# ARMBAND.net
KiCad netlist of a schematic drawn in Altium Designer
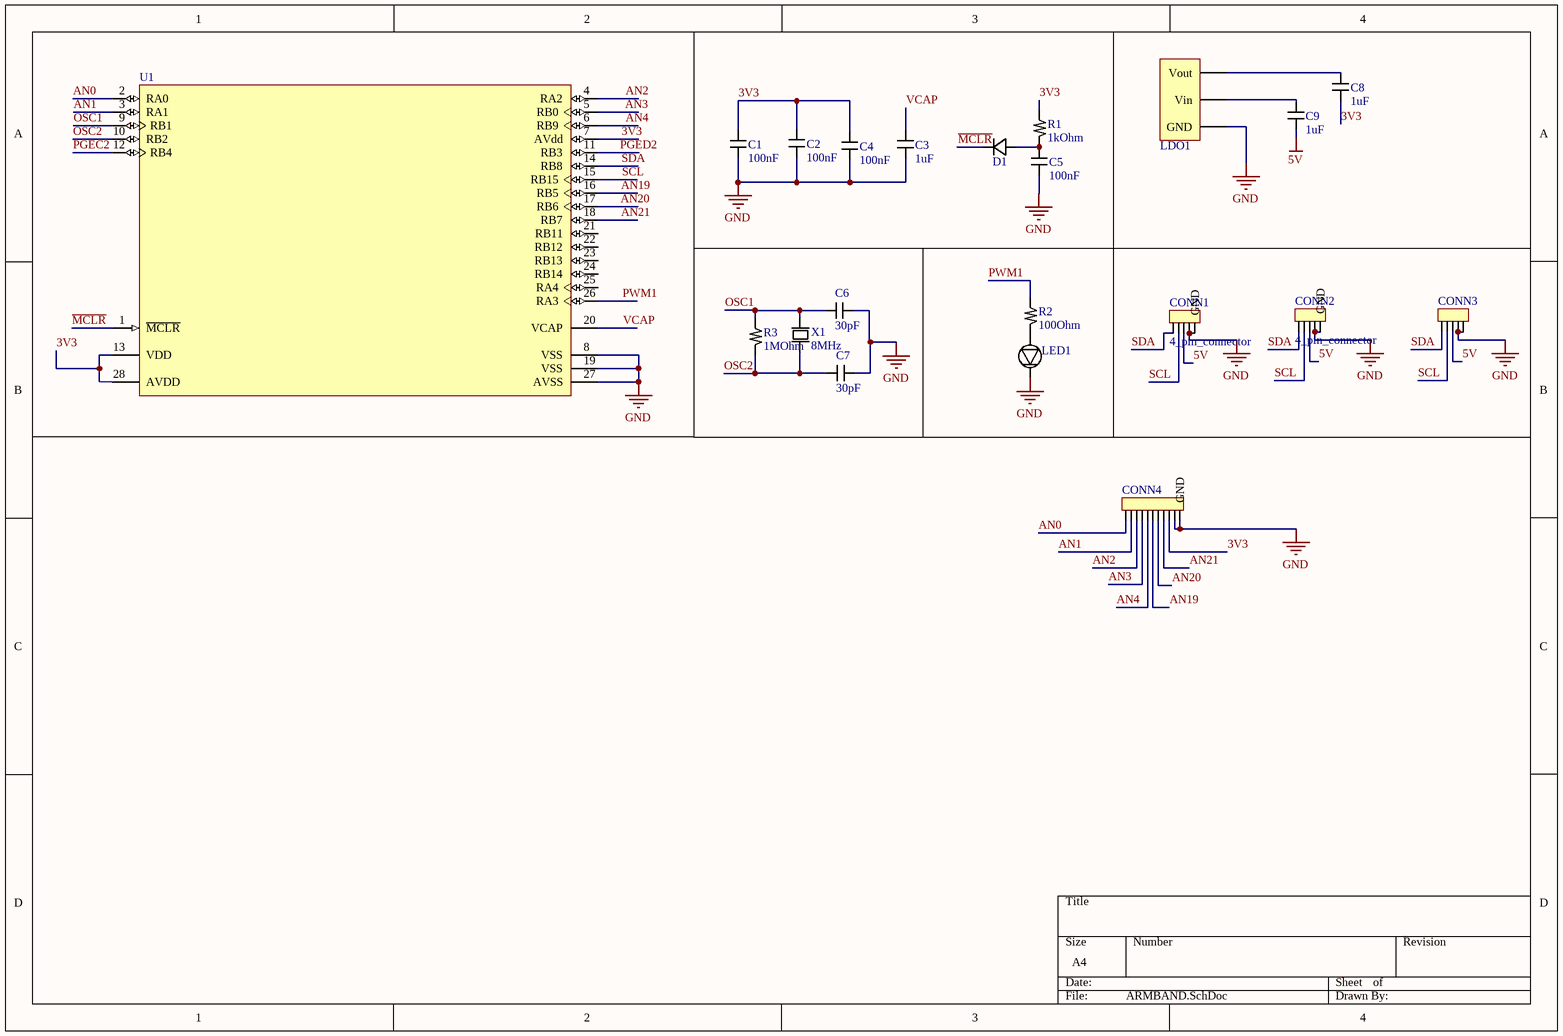
[diagram p0: ARMBAND.SchDoc]

(export (version "E")
  (design (tool "Eeschema 10.0.6"))
  (components
    (comp (ref "C1")
      (value "100nF")
      (footprint "CApacitor_1608")
      (description "SMD Capacitor")
      (libsource (lib "ARMBand_Components") (part "Capacitor_SMD"))
    )
    (comp (ref "C2")
      (value "100nF")
      (footprint "CApacitor_1608")
      (description "SMD Capacitor")
      (libsource (lib "ARMBand_Components") (part "Capacitor_SMD"))
    )
    (comp (ref "C3")
      (value "1uF")
      (footprint "Capacitor_20x12")
      (description "SMD Capacitor")
      (libsource (lib "ARMBand_Components") (part "Capacitor_SMD"))
    )
    (comp (ref "C4")
      (value "100nF")
      (footprint "CApacitor_1608")
      (description "SMD Capacitor")
      (libsource (lib "ARMBand_Components") (part "Capacitor_SMD"))
    )
    (comp (ref "C5")
      (value "100nF")
      (footprint "CApacitor_1608")
      (description "SMD Capacitor")
      (libsource (lib "ARMBand_Components") (part "Capacitor_SMD"))
    )
    (comp (ref "C6")
      (value "30pF")
      (footprint "CApacitor_1608")
      (description "SMD Capacitor")
      (libsource (lib "ARMBand_Components") (part "Capacitor_SMD"))
    )
    (comp (ref "C7")
      (value "30pF")
      (footprint "CApacitor_1608")
      (description "SMD Capacitor")
      (libsource (lib "ARMBand_Components") (part "Capacitor_SMD"))
    )
    (comp (ref "C8")
      (value "1uF")
      (footprint "Capacitor_20x12")
      (description "SMD Capacitor")
      (libsource (lib "ARMBand_Components") (part "Capacitor_SMD"))
    )
    (comp (ref "C9")
      (value "1uF")
      (footprint "Capacitor_20x12")
      (description "SMD Capacitor")
      (libsource (lib "ARMBand_Components") (part "Capacitor_SMD"))
    )
    (comp (ref "CONN1")
      (value "4_pin_connector")
      (footprint "4PIN_1MMPITCH_FFC_FCP_ZIF")
      (description "4 Pin Connector")
      (libsource (lib "") (part "4_pin_connector_1"))
    )
    (comp (ref "CONN2")
      (value "4_pin_connector")
      (footprint "4PIN_1MMPITCH_FFC_FCP_ZIF")
      (description "4 Pin Connector")
      (libsource (lib "") (part "4_pin_connector_1"))
    )
    (comp (ref "CONN3")
      (value "4_pin_connector")
      (footprint "4Pin_PICO_EZ_MATE_Header")
      (description "4 Pin Connector")
      (libsource (lib "ARMBand_Components") (part "4_pin_connector"))
    )
    (comp (ref "CONN4")
      (value "10_pin_connector")
      (footprint "10Pin_1mmpitch_FFC_FCP_ZIF")
      (description "10 Pin Connector")
      (libsource (lib "ARMBand_Components") (part "10_pin_connector"))
    )
    (comp (ref "D1")
      (value "Diode_SMD")
      (footprint "DIODE_17x38")
      (description "SMD Diode")
      (libsource (lib "ARMBand_Components") (part "Diode_SMD"))
    )
    (comp (ref "LDO1")
      (value "Voltage Reg.")
      (footprint "LDO_460x260")
      (description "LDO Voltage Regulator")
      (libsource (lib "ARMBand_Components") (part "Voltage_Regulator_3.3V"))
    )
    (comp (ref "LED1")
      (value "LED_SMD")
      (footprint "LED_1608")
      (description "SMD Blue LED")
      (libsource (lib "ARMBand_Components") (part "LED_SMD"))
    )
    (comp (ref "R1")
      (value "1kOhm")
      (footprint "Resistor_1608")
      (description "SMD Resistor")
      (libsource (lib "ARMBand_Components") (part "Resistor_SMD"))
    )
    (comp (ref "R2")
      (value "100Ohm")
      (footprint "Resistor_1608")
      (description "SMD Resistor")
      (libsource (lib "ARMBand_Components") (part "Resistor_SMD"))
    )
    (comp (ref "R3")
      (value "1MOhm")
      (footprint "Resistor_1608")
      (description "SMD Resistor")
      (libsource (lib "ARMBand_Components") (part "Resistor_SMD"))
    )
    (comp (ref "U1")
      (value "DSPIC33EP128MC202-I/SO")
      (footprint "MCHP-SOIC-SO28_N")
      (fields (field (name "MANUFACTURER") "Microchip"))
      (libsource (lib "Microchip dsPIC33E") (part "DSPIC33EP128MC202-I/SO"))
    )
    (comp (ref "X1")
      (value "8MHz")
      (footprint "xTal_150x20")
      (description "8MHz Crystal/Resonator")
      (libsource (lib "ARMBand_Components") (part "xTal_ECS_inc"))
    )
  )
  (nets
    (net (code "1") (name "/3V3") (class "Default")
      (node (ref "C1") (pin "Cap_p1") (pinfunction "Cap_p1_Cap_p1") (pintype "passive"))
      (node (ref "C2") (pin "Cap_p1") (pinfunction "Cap_p1_Cap_p1") (pintype "passive"))
      (node (ref "C4") (pin "Cap_p1") (pinfunction "Cap_p1_Cap_p1") (pintype "passive"))
      (node (ref "C8") (pin "Cap_p1") (pinfunction "Cap_p1_Cap_p1") (pintype "passive"))
      (node (ref "CONN4") (pin "9") (pinfunction "9_9") (pintype "passive"))
      (node (ref "R1") (pin "Res_p1") (pinfunction "Res_p1_Res_p1") (pintype "passive"))
      (node (ref "U1") (pin "13") (pinfunction "VDD_13") (pintype "power_in"))
      (node (ref "U1") (pin "28") (pinfunction "AVDD_28") (pintype "power_in"))
      (node (ref "U1") (pin "7") (pinfunction "AVdd_7") (pintype "bidirectional"))
    )
    (net (code "3") (name "/AN0") (class "Default")
      (node (ref "CONN4") (pin "1") (pinfunction "1_1") (pintype "passive"))
      (node (ref "U1") (pin "2") (pinfunction "RA0_2") (pintype "bidirectional"))
    )
    (net (code "4") (name "/AN1") (class "Default")
      (node (ref "CONN4") (pin "2") (pinfunction "2_2") (pintype "passive"))
      (node (ref "U1") (pin "3") (pinfunction "RA1_3") (pintype "bidirectional"))
    )
    (net (code "5") (name "/AN2") (class "Default")
      (node (ref "CONN4") (pin "3") (pinfunction "3_3") (pintype "passive"))
      (node (ref "U1") (pin "4") (pinfunction "RA2_4") (pintype "bidirectional"))
    )
    (net (code "6") (name "/AN3") (class "Default")
      (node (ref "CONN4") (pin "4") (pinfunction "4_4") (pintype "passive"))
      (node (ref "U1") (pin "5") (pinfunction "RB0_5") (pintype "bidirectional"))
    )
    (net (code "7") (name "/AN4") (class "Default")
      (node (ref "CONN4") (pin "5") (pinfunction "5_5") (pintype "passive"))
      (node (ref "U1") (pin "6") (pinfunction "RB9_6") (pintype "bidirectional"))
    )
    (net (code "8") (name "/AN19") (class "Default")
      (node (ref "CONN4") (pin "6") (pinfunction "6_6") (pintype "passive"))
      (node (ref "U1") (pin "16") (pinfunction "RB5_16") (pintype "bidirectional"))
    )
    (net (code "9") (name "/AN20") (class "Default")
      (node (ref "CONN4") (pin "7") (pinfunction "7_7") (pintype "passive"))
      (node (ref "U1") (pin "17") (pinfunction "RB6_17") (pintype "bidirectional"))
    )
    (net (code "10") (name "/AN21") (class "Default")
      (node (ref "CONN4") (pin "8") (pinfunction "8_8") (pintype "passive"))
      (node (ref "U1") (pin "18") (pinfunction "RB7_18") (pintype "bidirectional"))
    )
    (net (code "11") (name "/OSC1") (class "Default")
      (node (ref "C6") (pin "Cap_p2") (pinfunction "Cap_p2_Cap_p2") (pintype "passive"))
      (node (ref "R3") (pin "Res_p1") (pinfunction "Res_p1_Res_p1") (pintype "passive"))
      (node (ref "U1") (pin "9") (pinfunction "RB1_9") (pintype "bidirectional"))
      (node (ref "X1") (pin "xTal_0") (pinfunction "xTal_0_xTal_0") (pintype "passive"))
    )
    (net (code "12") (name "/OSC2") (class "Default")
      (node (ref "C7") (pin "Cap_p2") (pinfunction "Cap_p2_Cap_p2") (pintype "passive"))
      (node (ref "R3") (pin "Res_p2") (pinfunction "Res_p2_Res_p2") (pintype "passive"))
      (node (ref "U1") (pin "10") (pinfunction "RB2_10") (pintype "bidirectional"))
      (node (ref "X1") (pin "xTal_1") (pinfunction "xTal_1_xTal_1") (pintype "passive"))
    )
    (net (code "13") (name "/PGEC2") (class "Default")
      (node (ref "U1") (pin "12") (pinfunction "RB4_12") (pintype "bidirectional"))
    )
    (net (code "14") (name "/PGED2") (class "Default")
      (node (ref "U1") (pin "11") (pinfunction "RB3_11") (pintype "bidirectional"))
    )
    (net (code "15") (name "/PWM1") (class "Default")
      (node (ref "R2") (pin "Res_p1") (pinfunction "Res_p1_Res_p1") (pintype "passive"))
      (node (ref "U1") (pin "26") (pinfunction "RA3_26") (pintype "bidirectional"))
    )
    (net (code "16") (name "/SCL") (class "Default")
      (node (ref "CONN1") (pin "2") (pinfunction "2_2") (pintype "passive"))
      (node (ref "CONN2") (pin "2") (pinfunction "2_2") (pintype "passive"))
      (node (ref "CONN3") (pin "2") (pinfunction "2_2") (pintype "passive"))
      (node (ref "U1") (pin "15") (pinfunction "RB15_15") (pintype "bidirectional"))
    )
    (net (code "17") (name "/SDA") (class "Default")
      (node (ref "CONN1") (pin "1") (pinfunction "1_1") (pintype "passive"))
      (node (ref "CONN2") (pin "1") (pinfunction "1_1") (pintype "passive"))
      (node (ref "CONN3") (pin "1") (pinfunction "1_1") (pintype "passive"))
      (node (ref "U1") (pin "14") (pinfunction "RB8_14") (pintype "bidirectional"))
    )
    (net (code "18") (name "/VCAP") (class "Default")
      (node (ref "C3") (pin "Cap_p1") (pinfunction "Cap_p1_Cap_p1") (pintype "passive"))
      (node (ref "U1") (pin "20") (pinfunction "VCAP_20") (pintype "passive"))
    )
    (net (code "19") (name "/~{MCLR}") (class "Default")
      (node (ref "D1") (pin "Cathode") (pinfunction "Cathode_Cathode") (pintype "passive"))
      (node (ref "U1") (pin "1") (pinfunction "~{MCLR}_1") (pintype "input"))
    )
    (net (code "20") (name "5V") (class "Default")
      (node (ref "C9") (pin "Cap_p1") (pinfunction "Cap_p1_Cap_p1") (pintype "passive"))
      (node (ref "CONN1") (pin "3") (pinfunction "3_3") (pintype "passive"))
      (node (ref "CONN2") (pin "3") (pinfunction "3_3") (pintype "passive"))
      (node (ref "CONN3") (pin "3") (pinfunction "3_3") (pintype "passive"))
    )
    (net (code "21") (name "GND") (class "Default")
      (node (ref "C1") (pin "Cap_p2") (pinfunction "Cap_p2_Cap_p2") (pintype "passive"))
      (node (ref "C2") (pin "Cap_p2") (pinfunction "Cap_p2_Cap_p2") (pintype "passive"))
      (node (ref "C3") (pin "Cap_p2") (pinfunction "Cap_p2_Cap_p2") (pintype "passive"))
      (node (ref "C4") (pin "Cap_p2") (pinfunction "Cap_p2_Cap_p2") (pintype "passive"))
      (node (ref "C5") (pin "Cap_p2") (pinfunction "Cap_p2_Cap_p2") (pintype "passive"))
      (node (ref "C6") (pin "Cap_p1") (pinfunction "Cap_p1_Cap_p1") (pintype "passive"))
      (node (ref "C7") (pin "Cap_p1") (pinfunction "Cap_p1_Cap_p1") (pintype "passive"))
      (node (ref "CONN1") (pin "4") (pinfunction "4_4") (pintype "passive"))
      (node (ref "CONN1") (pin "GND") (pinfunction "GND_GND") (pintype "passive"))
      (node (ref "CONN2") (pin "4") (pinfunction "4_4") (pintype "passive"))
      (node (ref "CONN2") (pin "GND") (pinfunction "GND_GND") (pintype "passive"))
      (node (ref "CONN3") (pin "4") (pinfunction "4_4") (pintype "passive"))
      (node (ref "CONN3") (pin "GND") (pinfunction "GND_GND") (pintype "passive"))
      (node (ref "CONN4") (pin "10") (pinfunction "10_10") (pintype "passive"))
      (node (ref "CONN4") (pin "GND") (pinfunction "GND_GND") (pintype "passive"))
      (node (ref "LDO1") (pin "GND") (pinfunction "GND_GND") (pintype "passive"))
      (node (ref "LED1") (pin "Cathode") (pinfunction "Cathode_Cathode") (pintype "passive"))
      (node (ref "U1") (pin "19") (pinfunction "VSS_19") (pintype "power_in"))
      (node (ref "U1") (pin "27") (pinfunction "AVSS_27") (pintype "power_in"))
      (node (ref "U1") (pin "8") (pinfunction "VSS_8") (pintype "power_in"))
    )
    (net (code "22") (name "Net-(C5-PadCap_p1)") (class "Default")
      (node (ref "C5") (pin "Cap_p1") (pinfunction "Cap_p1_Cap_p1") (pintype "passive"))
      (node (ref "D1") (pin "Anode") (pinfunction "Anode_Anode") (pintype "passive"))
      (node (ref "R1") (pin "Res_p2") (pinfunction "Res_p2_Res_p2") (pintype "passive"))
    )
    (net (code "23") (name "Net-(C8-PadCap_p2)") (class "Default")
      (node (ref "C8") (pin "Cap_p2") (pinfunction "Cap_p2_Cap_p2") (pintype "passive"))
      (node (ref "LDO1") (pin "Vout") (pinfunction "Vout_Vout") (pintype "passive"))
    )
    (net (code "24") (name "Net-(C9-PadCap_p2)") (class "Default")
      (node (ref "C9") (pin "Cap_p2") (pinfunction "Cap_p2_Cap_p2") (pintype "passive"))
      (node (ref "LDO1") (pin "Vin") (pinfunction "Vin_Vin") (pintype "passive"))
    )
    (net (code "25") (name "Net-(LED1-PadAnode)") (class "Default")
      (node (ref "LED1") (pin "Anode") (pinfunction "Anode_Anode") (pintype "passive"))
      (node (ref "R2") (pin "Res_p2") (pinfunction "Res_p2_Res_p2") (pintype "passive"))
    )
    (net (code "26") (name "unconnected-(U1-RA4-Pad25)") (class "Default")
      (node (ref "U1") (pin "25") (pinfunction "RA4_25") (pintype "bidirectional"))
    )
    (net (code "27") (name "unconnected-(U1-RB11-Pad21)") (class "Default")
      (node (ref "U1") (pin "21") (pinfunction "RB11_21") (pintype "bidirectional"))
    )
    (net (code "28") (name "unconnected-(U1-RB12-Pad22)") (class "Default")
      (node (ref "U1") (pin "22") (pinfunction "RB12_22") (pintype "bidirectional"))
    )
    (net (code "29") (name "unconnected-(U1-RB13-Pad23)") (class "Default")
      (node (ref "U1") (pin "23") (pinfunction "RB13_23") (pintype "bidirectional"))
    )
    (net (code "30") (name "unconnected-(U1-RB14-Pad24)") (class "Default")
      (node (ref "U1") (pin "24") (pinfunction "RB14_24") (pintype "bidirectional"))
    )
  )
)
